# PY32.net
KiCad netlist of a schematic drawn in EasyEDA Pro
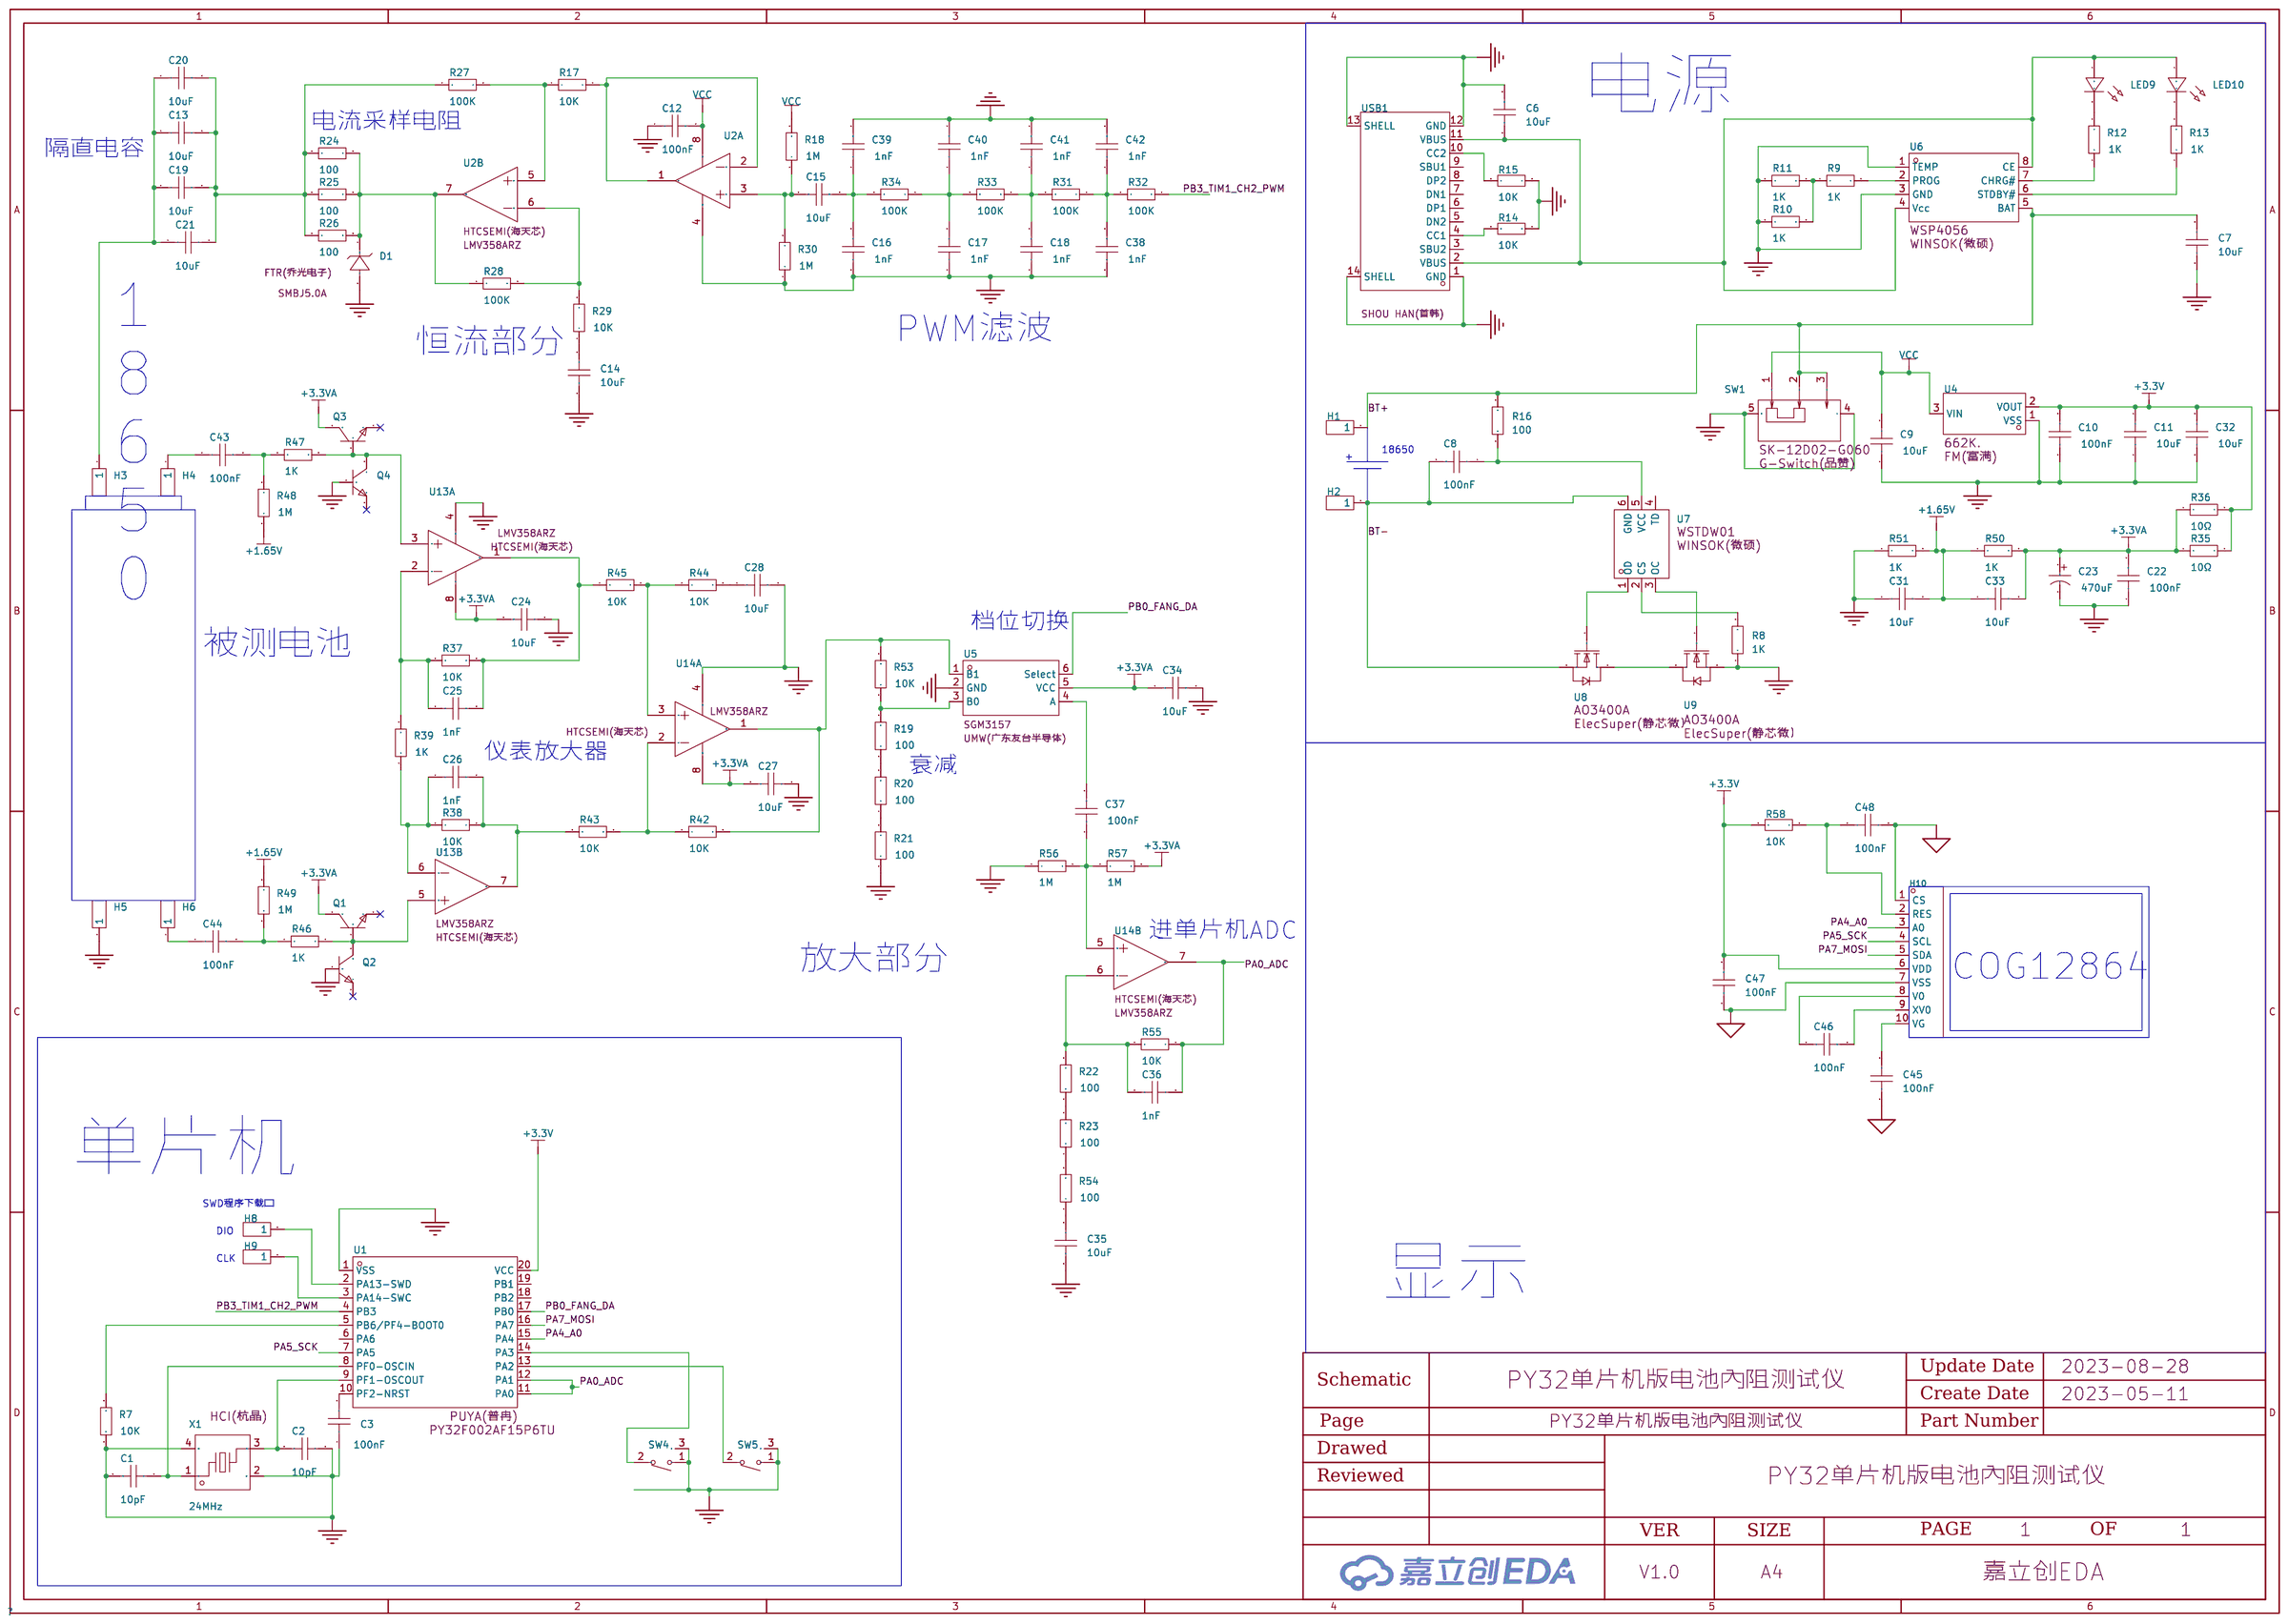
[diagram p0: schematic sheet]

(export (version "E")
  (design (tool "Eeschema 10.0.6"))
  (components
    (comp (ref "C1")
      (value "10pF")
      (footprint "easyedapro:C0603")
      (libsource (lib "easyedapro") (part "CapAcitance"))
    )
    (comp (ref "C2")
      (value "10pF")
      (footprint "easyedapro:C0603")
      (libsource (lib "easyedapro") (part "CapAcitance"))
    )
    (comp (ref "C3")
      (value "100nF")
      (footprint "easyedapro:C0603")
      (libsource (lib "easyedapro") (part "CapAcitance"))
    )
    (comp (ref "C6")
      (value "10uF")
      (footprint "easyedapro:C0603")
      (libsource (lib "easyedapro") (part "CapAcitance"))
    )
    (comp (ref "C7")
      (value "10uF")
      (footprint "easyedapro:C0603")
      (libsource (lib "easyedapro") (part "CapAcitance"))
    )
    (comp (ref "C8")
      (value "100nF")
      (footprint "easyedapro:C0603")
      (libsource (lib "easyedapro") (part "CapAcitance"))
    )
    (comp (ref "C9")
      (value "10uF")
      (footprint "easyedapro:C0603")
      (libsource (lib "easyedapro") (part "CapAcitance"))
    )
    (comp (ref "C10")
      (value "100nF")
      (footprint "easyedapro:C0603")
      (libsource (lib "easyedapro") (part "CapAcitance"))
    )
    (comp (ref "C11")
      (value "10uF")
      (footprint "easyedapro:C0603")
      (libsource (lib "easyedapro") (part "CapAcitance"))
    )
    (comp (ref "C12")
      (value "100nF")
      (footprint "easyedapro:C0603")
      (libsource (lib "easyedapro") (part "CapAcitance"))
    )
    (comp (ref "C13")
      (value "10uF")
      (footprint "easyedapro:C0603")
      (libsource (lib "easyedapro") (part "CapAcitance"))
    )
    (comp (ref "C14")
      (value "10uF")
      (footprint "easyedapro:C0603")
      (libsource (lib "easyedapro") (part "CapAcitance"))
    )
    (comp (ref "C15")
      (value "10uF")
      (footprint "easyedapro:C0603")
      (libsource (lib "easyedapro") (part "CapAcitance"))
    )
    (comp (ref "C16")
      (value "1nF")
      (footprint "easyedapro:C0603")
      (libsource (lib "easyedapro") (part "CapAcitance"))
    )
    (comp (ref "C17")
      (value "1nF")
      (footprint "easyedapro:C0603")
      (libsource (lib "easyedapro") (part "CapAcitance"))
    )
    (comp (ref "C18")
      (value "1nF")
      (footprint "easyedapro:C0603")
      (libsource (lib "easyedapro") (part "CapAcitance"))
    )
    (comp (ref "C19")
      (value "10uF")
      (footprint "easyedapro:C0603")
      (libsource (lib "easyedapro") (part "CapAcitance"))
    )
    (comp (ref "C20")
      (value "10uF")
      (footprint "easyedapro:C0603")
      (libsource (lib "easyedapro") (part "CapAcitance"))
    )
    (comp (ref "C21")
      (value "10uF")
      (footprint "easyedapro:C0603")
      (libsource (lib "easyedapro") (part "CapAcitance"))
    )
    (comp (ref "C22")
      (value "100nF")
      (footprint "easyedapro:C0603")
      (libsource (lib "easyedapro") (part "CapAcitance"))
    )
    (comp (ref "C23")
      (value "470uF")
      (footprint "easyedapro:CAP-TH_BD8.0-P3.50-D0.6-FD")
      (description "容值:470uF;精度:±20%;额定电压:16V;")
      (fields
        (field (name "Manufacturer Part") "KM477M016F12RR0VH2FP0")
        (field (name "Manufacturer") "CX(承兴)")
      )
      (libsource (lib "easyedapro") (part "470uf16v"))
    )
    (comp (ref "C24")
      (value "10uF")
      (footprint "easyedapro:C0603")
      (libsource (lib "easyedapro") (part "CapAcitance"))
    )
    (comp (ref "C25")
      (value "1nF")
      (footprint "easyedapro:C0603")
      (libsource (lib "easyedapro") (part "CapAcitance"))
    )
    (comp (ref "C26")
      (value "1nF")
      (footprint "easyedapro:C0603")
      (libsource (lib "easyedapro") (part "CapAcitance"))
    )
    (comp (ref "C27")
      (value "10uF")
      (footprint "easyedapro:C0603")
      (libsource (lib "easyedapro") (part "CapAcitance"))
    )
    (comp (ref "C28")
      (value "10uF")
      (footprint "easyedapro:C0603")
      (libsource (lib "easyedapro") (part "CapAcitance"))
    )
    (comp (ref "C31")
      (value "10uF")
      (footprint "easyedapro:C0603")
      (libsource (lib "easyedapro") (part "CapAcitance"))
    )
    (comp (ref "C32")
      (value "10uF")
      (footprint "easyedapro:C0603")
      (libsource (lib "easyedapro") (part "CapAcitance"))
    )
    (comp (ref "C33")
      (value "10uF")
      (footprint "easyedapro:C0603")
      (libsource (lib "easyedapro") (part "CapAcitance"))
    )
    (comp (ref "C34")
      (value "10uF")
      (footprint "easyedapro:C0603")
      (libsource (lib "easyedapro") (part "CapAcitance"))
    )
    (comp (ref "C35")
      (value "10uF")
      (footprint "easyedapro:C0603")
      (libsource (lib "easyedapro") (part "CapAcitance"))
    )
    (comp (ref "C36")
      (value "1nF")
      (footprint "easyedapro:C0603")
      (libsource (lib "easyedapro") (part "CapAcitance"))
    )
    (comp (ref "C37")
      (value "100nF")
      (footprint "easyedapro:C0603")
      (libsource (lib "easyedapro") (part "CapAcitance"))
    )
    (comp (ref "C38")
      (value "1nF")
      (footprint "easyedapro:C0603")
      (libsource (lib "easyedapro") (part "CapAcitance"))
    )
    (comp (ref "C39")
      (value "1nF")
      (footprint "easyedapro:C0603")
      (libsource (lib "easyedapro") (part "CapAcitance"))
    )
    (comp (ref "C40")
      (value "1nF")
      (footprint "easyedapro:C0603")
      (libsource (lib "easyedapro") (part "CapAcitance"))
    )
    (comp (ref "C41")
      (value "1nF")
      (footprint "easyedapro:C0603")
      (libsource (lib "easyedapro") (part "CapAcitance"))
    )
    (comp (ref "C42")
      (value "1nF")
      (footprint "easyedapro:C0603")
      (libsource (lib "easyedapro") (part "CapAcitance"))
    )
    (comp (ref "C43")
      (value "100nF")
      (footprint "easyedapro:C1206")
      (description "容值:100nF;精度:±10%;额定电压:450V;材质(温度系数):X7R;")
      (fields (field (name "Manufacturer Part") "FM31X104K451EEG") (field (name "Manufacturer") "PSA(信昌电陶)"))
      (libsource (lib "easyedapro") (part "FM31X104K451EEG"))
    )
    (comp (ref "C44")
      (value "100nF")
      (footprint "easyedapro:C1206")
      (description "容值:100nF;精度:±10%;额定电压:450V;材质(温度系数):X7R;")
      (fields (field (name "Manufacturer Part") "FM31X104K451EEG") (field (name "Manufacturer") "PSA(信昌电陶)"))
      (libsource (lib "easyedapro") (part "FM31X104K451EEG"))
    )
    (comp (ref "C45")
      (value "100nF")
      (footprint "easyedapro:C0603")
      (libsource (lib "easyedapro") (part "CapAcitance"))
    )
    (comp (ref "C46")
      (value "100nF")
      (footprint "easyedapro:C0603")
      (libsource (lib "easyedapro") (part "CapAcitance"))
    )
    (comp (ref "C47")
      (value "100nF")
      (footprint "easyedapro:C0603")
      (libsource (lib "easyedapro") (part "CapAcitance"))
    )
    (comp (ref "C48")
      (value "100nF")
      (footprint "easyedapro:C0603")
      (libsource (lib "easyedapro") (part "CapAcitance"))
    )
    (comp (ref "D1")
      (value "SMBJ5.0A")
      (footprint "easyedapro:SMB_L4.3-W3.6-LS5.3-RD")
      (description "极性:单向;反向截止电压(Vrwm):5V;击穿电压(最小值):6.4V;峰值脉冲电流(Ipp)@10/1000s:65.3A;最大钳位电压:9.2V;")
      (fields (field (name "Manufacturer Part") "SMBJ5.0A") (field (name "Manufacturer") "FTR(乔光电子)"))
      (libsource (lib "easyedapro") (part "SMBJ5.0A_C693503"))
    )
    (comp (ref "H1")
      (value "~")
      (footprint "easyedapro:HDR-TH_1P-V-M_XKB_X4611WV-01I-C28D40")
      (libsource (lib "easyedapro") (part "HDR_1x1"))
    )
    (comp (ref "H2")
      (value "~")
      (footprint "easyedapro:HDR-TH_1P-V-M_XKB_X4611WV-01I-C28D40")
      (libsource (lib "easyedapro") (part "HDR_1x1"))
    )
    (comp (ref "H3")
      (value "~")
      (footprint "easyedapro:HDR-TH_1P-V-M_XKB_X4611WV-01I-C28D40")
      (libsource (lib "easyedapro") (part "HDR_1x1"))
    )
    (comp (ref "H4")
      (value "~")
      (footprint "easyedapro:HDR-TH_1P-V-M_XKB_X4611WV-01I-C28D40")
      (libsource (lib "easyedapro") (part "HDR_1x1"))
    )
    (comp (ref "H5")
      (value "~")
      (footprint "easyedapro:HDR-TH_1P-V-M_XKB_X4611WV-01I-C28D40")
      (libsource (lib "easyedapro") (part "HDR_1x1"))
    )
    (comp (ref "H6")
      (value "~")
      (footprint "easyedapro:HDR-TH_1P-V-M_XKB_X4611WV-01I-C28D40")
      (libsource (lib "easyedapro") (part "HDR_1x1"))
    )
    (comp (ref "H8")
      (value "~")
      (footprint "easyedapro:HDR-TH_1P-V-M_XKB_X4611WV-01I-C28D40")
      (libsource (lib "easyedapro") (part "HDR_1x1"))
    )
    (comp (ref "H9")
      (value "~")
      (footprint "easyedapro:HDR-TH_1P-V-M_XKB_X4611WV-01I-C28D40")
      (libsource (lib "easyedapro") (part "HDR_1x1"))
    )
    (comp (ref "H10")
      (value "~")
      (footprint "easyedapro:HDR-TH_10P-P2.54-V-M-1")
      (fields (field (name "Manufacturer Part") "2.54-1*10P针") (field (name "Manufacturer") "BOOMELE(博穆精密)"))
      (libsource (lib "easyedapro") (part "Header-Male-2.54_1x10"))
    )
    (comp (ref "LED9")
      (value "~")
      (footprint "easyedapro:LED_TH-3mm")
      (libsource (lib "easyedapro") (part "LED_TH-R"))
    )
    (comp (ref "LED10")
      (value "~")
      (footprint "easyedapro:LED_TH-3mm")
      (libsource (lib "easyedapro") (part "LED_TH-R"))
    )
    (comp (ref "Q1")
      (value "SS8050")
      (footprint "easyedapro:SOT-23-3_L2.9-W1.3-P1.90-LS2.4-BR")
      (fields (field (name "Manufacturer") "ElecSuper(静芯微）"))
      (libsource (lib "easyedapro") (part "SS8050_C5249676"))
    )
    (comp (ref "Q2")
      (value "SS8050")
      (footprint "easyedapro:SOT-23-3_L2.9-W1.3-P1.90-LS2.4-BR")
      (fields (field (name "Manufacturer") "ElecSuper(静芯微）"))
      (libsource (lib "easyedapro") (part "SS8050_C5249676"))
    )
    (comp (ref "Q3")
      (value "SS8050")
      (footprint "easyedapro:SOT-23-3_L2.9-W1.3-P1.90-LS2.4-BR")
      (fields (field (name "Manufacturer") "ElecSuper(静芯微）"))
      (libsource (lib "easyedapro") (part "SS8050_C5249676"))
    )
    (comp (ref "Q4")
      (value "SS8050")
      (footprint "easyedapro:SOT-23-3_L2.9-W1.3-P1.90-LS2.4-BR")
      (fields (field (name "Manufacturer") "ElecSuper(静芯微）"))
      (libsource (lib "easyedapro") (part "SS8050_C5249676"))
    )
    (comp (ref "R7") (value "10K") (footprint "easyedapro:R0603") (libsource (lib "easyedapro") (part "电阻")))
    (comp (ref "R8") (value "1K") (footprint "easyedapro:R0603") (libsource (lib "easyedapro") (part "电阻")))
    (comp (ref "R9") (value "1K") (footprint "easyedapro:R0603") (libsource (lib "easyedapro") (part "电阻")))
    (comp (ref "R10") (value "1K") (footprint "easyedapro:R0603") (libsource (lib "easyedapro") (part "电阻")))
    (comp (ref "R11") (value "1K") (footprint "easyedapro:R0603") (libsource (lib "easyedapro") (part "电阻")))
    (comp (ref "R12") (value "1K") (footprint "easyedapro:R0603") (libsource (lib "easyedapro") (part "电阻")))
    (comp (ref "R13") (value "1K") (footprint "easyedapro:R0603") (libsource (lib "easyedapro") (part "电阻")))
    (comp (ref "R14") (value "10K") (footprint "easyedapro:R0603") (libsource (lib "easyedapro") (part "电阻")))
    (comp (ref "R15") (value "10K") (footprint "easyedapro:R0603") (libsource (lib "easyedapro") (part "电阻")))
    (comp (ref "R16") (value "100") (footprint "easyedapro:R0603") (libsource (lib "easyedapro") (part "电阻")))
    (comp (ref "R17") (value "10K") (footprint "easyedapro:R0603") (libsource (lib "easyedapro") (part "电阻")))
    (comp (ref "R18") (value "1M") (footprint "easyedapro:R0603") (libsource (lib "easyedapro") (part "电阻")))
    (comp (ref "R19") (value "100") (footprint "easyedapro:R0603") (libsource (lib "easyedapro") (part "电阻")))
    (comp (ref "R20") (value "100") (footprint "easyedapro:R0603") (libsource (lib "easyedapro") (part "电阻")))
    (comp (ref "R21") (value "100") (footprint "easyedapro:R0603") (libsource (lib "easyedapro") (part "电阻")))
    (comp (ref "R22") (value "100") (footprint "easyedapro:R0603") (libsource (lib "easyedapro") (part "电阻")))
    (comp (ref "R23") (value "100") (footprint "easyedapro:R0603") (libsource (lib "easyedapro") (part "电阻")))
    (comp (ref "R24") (value "100") (footprint "easyedapro:R0603") (libsource (lib "easyedapro") (part "电阻")))
    (comp (ref "R25") (value "100") (footprint "easyedapro:R0603") (libsource (lib "easyedapro") (part "电阻")))
    (comp (ref "R26") (value "100") (footprint "easyedapro:R0603") (libsource (lib "easyedapro") (part "电阻")))
    (comp (ref "R27")
      (value "100K")
      (footprint "easyedapro:R0603")
      (libsource (lib "easyedapro") (part "电阻"))
    )
    (comp (ref "R28")
      (value "100K")
      (footprint "easyedapro:R0603")
      (libsource (lib "easyedapro") (part "电阻"))
    )
    (comp (ref "R29") (value "10K") (footprint "easyedapro:R0603") (libsource (lib "easyedapro") (part "电阻")))
    (comp (ref "R30") (value "1M") (footprint "easyedapro:R0603") (libsource (lib "easyedapro") (part "电阻")))
    (comp (ref "R31")
      (value "100K")
      (footprint "easyedapro:R0603")
      (libsource (lib "easyedapro") (part "电阻"))
    )
    (comp (ref "R32")
      (value "100K")
      (footprint "easyedapro:R0603")
      (libsource (lib "easyedapro") (part "电阻"))
    )
    (comp (ref "R33")
      (value "100K")
      (footprint "easyedapro:R0603")
      (libsource (lib "easyedapro") (part "电阻"))
    )
    (comp (ref "R34")
      (value "100K")
      (footprint "easyedapro:R0603")
      (libsource (lib "easyedapro") (part "电阻"))
    )
    (comp (ref "R35") (value "10Ω") (footprint "easyedapro:R0603") (libsource (lib "easyedapro") (part "电阻")))
    (comp (ref "R36") (value "10Ω") (footprint "easyedapro:R0603") (libsource (lib "easyedapro") (part "电阻")))
    (comp (ref "R37") (value "10K") (footprint "easyedapro:R0603") (libsource (lib "easyedapro") (part "电阻")))
    (comp (ref "R38") (value "10K") (footprint "easyedapro:R0603") (libsource (lib "easyedapro") (part "电阻")))
    (comp (ref "R39") (value "1K") (footprint "easyedapro:R0603") (libsource (lib "easyedapro") (part "电阻")))
    (comp (ref "R42") (value "10K") (footprint "easyedapro:R0603") (libsource (lib "easyedapro") (part "电阻")))
    (comp (ref "R43") (value "10K") (footprint "easyedapro:R0603") (libsource (lib "easyedapro") (part "电阻")))
    (comp (ref "R44") (value "10K") (footprint "easyedapro:R0603") (libsource (lib "easyedapro") (part "电阻")))
    (comp (ref "R45") (value "10K") (footprint "easyedapro:R0603") (libsource (lib "easyedapro") (part "电阻")))
    (comp (ref "R46") (value "1K") (footprint "easyedapro:R0603") (libsource (lib "easyedapro") (part "电阻")))
    (comp (ref "R47") (value "1K") (footprint "easyedapro:R0603") (libsource (lib "easyedapro") (part "电阻")))
    (comp (ref "R48") (value "1M") (footprint "easyedapro:R0603") (libsource (lib "easyedapro") (part "电阻")))
    (comp (ref "R49") (value "1M") (footprint "easyedapro:R0603") (libsource (lib "easyedapro") (part "电阻")))
    (comp (ref "R50") (value "1K") (footprint "easyedapro:R0603") (libsource (lib "easyedapro") (part "电阻")))
    (comp (ref "R51") (value "1K") (footprint "easyedapro:R0603") (libsource (lib "easyedapro") (part "电阻")))
    (comp (ref "R53") (value "10K") (footprint "easyedapro:R0603") (libsource (lib "easyedapro") (part "电阻")))
    (comp (ref "R54") (value "100") (footprint "easyedapro:R0603") (libsource (lib "easyedapro") (part "电阻")))
    (comp (ref "R55") (value "10K") (footprint "easyedapro:R0603") (libsource (lib "easyedapro") (part "电阻")))
    (comp (ref "R56") (value "1M") (footprint "easyedapro:R0603") (libsource (lib "easyedapro") (part "电阻")))
    (comp (ref "R57") (value "1M") (footprint "easyedapro:R0603") (libsource (lib "easyedapro") (part "电阻")))
    (comp (ref "R58") (value "10K") (footprint "easyedapro:R0603") (libsource (lib "easyedapro") (part "电阻")))
    (comp (ref "SW1")
      (value "SK-12D02-G060")
      (footprint "easyedapro:SW-TH_SK-12D02-G060")
      (description "额定电流(DC):1A;额定电压(DC):24V;电路结构:单刀双掷;安装方式:卧插;机械寿命:1万次;开关颜色:黑色;")
      (fields (field (name "Manufacturer Part") "SK-12D02-G060") (field (name "Manufacturer") "G-Switch(品赞)"))
      (libsource (lib "easyedapro") (part "SK-12D02-G060"))
    )
    (comp (ref "SW4")
      (value "HX TS4538B3J 250gf")
      (footprint "easyedapro:SW-TH_TS4538B3J")
      (description "机械寿命:-;")
      (fields (field (name "Manufacturer") "hanxia(韩下)"))
      (libsource (lib "easyedapro") (part "HX TS4538B3J 250GF"))
    )
    (comp (ref "SW5")
      (value "HX TS4538B3J 250gf")
      (footprint "easyedapro:SW-TH_TS4538B3J")
      (description "机械寿命:-;")
      (fields (field (name "Manufacturer") "hanxia(韩下)"))
      (libsource (lib "easyedapro") (part "HX TS4538B3J 250GF"))
    )
    (comp (ref "U1")
      (value "PY32F002AF15P6TU")
      (footprint "easyedapro:TSSOP-20_L6.5-W4.4-P0.65-LS6.4-BL")
      (fields (field (name "Manufacturer Part") "PY32F002AF15P6TU") (field (name "Manufacturer") "PUYA(普冉)"))
      (libsource (lib "easyedapro") (part "PY32F002AF15P6TU"))
    )
    (comp (ref "U2")
      (value "LMV358ARZ")
      (footprint "easyedapro:SOP-8_L4.9-W3.9-P1.27-LS6.0-BL")
      (description "CMOS低功耗双路运算放大器")
      (fields (field (name "Manufacturer Part") "LMV358ARZ") (field (name "Manufacturer") "HTCSEMI(海天芯)"))
      (libsource (lib "easyedapro") (part "LMV358ARZ"))
    )
    (comp (ref "U4")
      (value "662K.")
      (footprint "easyedapro:SOT-23-3_L2.9-W1.3-P1.90-LS2.4-BR")
      (description "输出类型:-;")
      (fields (field (name "Manufacturer Part") "662K.") (field (name "Manufacturer") "FM(富满)"))
      (libsource (lib "easyedapro") (part "662K."))
    )
    (comp (ref "U5")
      (value "SGM3157")
      (footprint "easyedapro:SC-70-6_L2.2-W1.3-P0.65-LS2.1-BL")
      (description "开关电路:-;")
      (fields (field (name "Manufacturer Part") "SGM3157") (field (name "Manufacturer") "UMW(广东友台半导体)"))
      (libsource (lib "easyedapro") (part "SGM3157"))
    )
    (comp (ref "U6")
      (value "WSP4056")
      (footprint "easyedapro:SOP-8_L5.1-W3.9-P1.27-LS6.0-BL")
      (fields (field (name "Manufacturer Part") "WSP4056") (field (name "Manufacturer") "WINSOK(微硕)"))
      (libsource (lib "easyedapro") (part "WSP4056"))
    )
    (comp (ref "U7")
      (value "WSTDW01")
      (footprint "easyedapro:SOT-23-6_L2.9-W1.6-P0.95-LS2.8-BR")
      (description "充电电池的类型:-;电池单元组数:-;最大充电电流:-;充满的电池组电压:-;最大供应电压:-;")
      (fields (field (name "Manufacturer Part") "WSTDW01") (field (name "Manufacturer") "WINSOK(微硕)"))
      (libsource (lib "easyedapro") (part "WSTDW01"))
    )
    (comp (ref "U8")
      (value "AO3400A")
      (footprint "easyedapro:SOT-23-3_L3.0-W1.6-P1.90-LS2.8-BR")
      (description "类型:N沟道;漏源电压(Vdss):30V;连续漏极电流(Id):6A;功率(Pd):1.4W;导通电阻(RDS(on)@Vgs,Id):19mΩ@10V,6.0A;")
      (fields (field (name "Manufacturer Part") "AO3400A") (field (name "Manufacturer") "ElecSuper(静芯微）"))
      (libsource (lib "easyedapro") (part "AO3400A_C5224194"))
    )
    (comp (ref "U9")
      (value "AO3400A")
      (footprint "easyedapro:SOT-23-3_L3.0-W1.6-P1.90-LS2.8-BR")
      (description "类型:N沟道;漏源电压(Vdss):30V;连续漏极电流(Id):6A;功率(Pd):1.4W;导通电阻(RDS(on)@Vgs,Id):19mΩ@10V,6.0A;")
      (fields (field (name "Manufacturer Part") "AO3400A") (field (name "Manufacturer") "ElecSuper(静芯微）"))
      (libsource (lib "easyedapro") (part "AO3400A_C5224194"))
    )
    (comp (ref "U13")
      (value "LMV358ARZ")
      (footprint "easyedapro:SOP-8_L4.9-W3.9-P1.27-LS6.0-BL")
      (description "CMOS低功耗双路运算放大器")
      (fields (field (name "Manufacturer Part") "LMV358ARZ") (field (name "Manufacturer") "HTCSEMI(海天芯)"))
      (libsource (lib "easyedapro") (part "LMV358ARZ"))
    )
    (comp (ref "U14")
      (value "LMV358ARZ")
      (footprint "easyedapro:SOP-8_L4.9-W3.9-P1.27-LS6.0-BL")
      (description "CMOS低功耗双路运算放大器")
      (fields (field (name "Manufacturer Part") "LMV358ARZ") (field (name "Manufacturer") "HTCSEMI(海天芯)"))
      (libsource (lib "easyedapro") (part "LMV358ARZ"))
    )
    (comp (ref "USB1")
      (value "TYPE-C 16PIN 2MD(073)")
      (footprint "easyedapro:USB-C-SMD_TYPE-C-6PIN-2MD-073")
      (description "连接器类型:Type-C;标准:-;公母:母座;触点数量:16;端口数量:1;安装方式:卧贴;额定电流 - 电源:5A;工作温度范围:-25°C~+85°C;")
      (fields (field (name "Manufacturer") "SHOU HAN(首韩)"))
      (libsource (lib "easyedapro") (part "TYPE-C 16PIN 2MD(073)"))
    )
    (comp (ref "X1")
      (value "24MHz")
      (footprint "easyedapro:CRYSTAL-SMD_4P-L3.2-W2.5-BL")
      (description "频率:24MHz;频率公差:±10ppm;频率稳定度:±30ppm;负载电容:12pF;")
      (fields
        (field (name "Manufacturer Part") "XC32M4-24.000-F12NJDTL")
        (field (name "Manufacturer") "HCI(杭晶)")
      )
      (libsource (lib "easyedapro") (part "XC32M4-24.000-F12NJDTL"))
    )
  )
  (nets
    (net (code "1") (name "+1.65V") (class "Default")
      (node (ref "C31") (pin "2") (pinfunction "2_2") (pintype "input"))
      (node (ref "C33") (pin "1") (pinfunction "1_1") (pintype "input"))
      (node (ref "R48") (pin "1") (pinfunction "1_1") (pintype "input"))
      (node (ref "R49") (pin "2") (pinfunction "2_2") (pintype "input"))
      (node (ref "R50") (pin "1") (pinfunction "1_1") (pintype "input"))
      (node (ref "R51") (pin "2") (pinfunction "2_2") (pintype "input"))
    )
    (net (code "2") (name "+3.3V") (class "Default")
      (node (ref "C10") (pin "2") (pinfunction "2_2") (pintype "input"))
      (node (ref "C11") (pin "2") (pinfunction "2_2") (pintype "input"))
      (node (ref "C32") (pin "2") (pinfunction "2_2") (pintype "input"))
      (node (ref "C47") (pin "2") (pinfunction "2_2") (pintype "input"))
      (node (ref "H10") (pin "6") (pinfunction "VDD_6") (pintype "input"))
      (node (ref "R35") (pin "2") (pinfunction "2_2") (pintype "input"))
      (node (ref "R36") (pin "2") (pinfunction "2_2") (pintype "input"))
      (node (ref "R58") (pin "1") (pinfunction "1_1") (pintype "input"))
      (node (ref "U1") (pin "20") (pinfunction "VCC_20") (pintype "input"))
      (node (ref "U4") (pin "2") (pinfunction "VOUT_2") (pintype "input"))
    )
    (net (code "3") (name "+3.3VA") (class "Default")
      (node (ref "C22") (pin "2") (pinfunction "2_2") (pintype "input"))
      (node (ref "C23") (pin "1") (pinfunction "1_1") (pintype "input"))
      (node (ref "C24") (pin "2") (pinfunction "2_2") (pintype "input"))
      (node (ref "C27") (pin "1") (pinfunction "1_1") (pintype "input"))
      (node (ref "C33") (pin "2") (pinfunction "2_2") (pintype "input"))
      (node (ref "C34") (pin "1") (pinfunction "1_1") (pintype "input"))
      (node (ref "Q1") (pin "3") (pinfunction "C_3") (pintype "input"))
      (node (ref "Q3") (pin "3") (pinfunction "C_3") (pintype "input"))
      (node (ref "R35") (pin "1") (pinfunction "1_1") (pintype "input"))
      (node (ref "R36") (pin "1") (pinfunction "1_1") (pintype "input"))
      (node (ref "R50") (pin "2") (pinfunction "2_2") (pintype "input"))
      (node (ref "R57") (pin "2") (pinfunction "2_2") (pintype "input"))
      (node (ref "U13") (pin "8") (pinfunction "VCC_8") (pintype "input"))
      (node (ref "U14") (pin "8") (pinfunction "VCC_8") (pintype "input"))
      (node (ref "U5") (pin "5") (pinfunction "VCC_5") (pintype "input"))
    )
    (net (code "4") (name "/BT+") (class "Default")
      (node (ref "C7") (pin "2") (pinfunction "2_2") (pintype "input"))
      (node (ref "H1") (pin "1") (pinfunction "1_1") (pintype "unspecified"))
      (node (ref "R16") (pin "2") (pinfunction "2_2") (pintype "input"))
      (node (ref "SW1") (pin "2") (pinfunction "2_2") (pintype "input"))
      (node (ref "SW1") (pin "3") (pinfunction "3_3") (pintype "input"))
      (node (ref "U6") (pin "5") (pinfunction "BAT_5") (pintype "input"))
    )
    (net (code "5") (name "/BT-") (class "Default")
      (node (ref "C8") (pin "2") (pinfunction "2_2") (pintype "input"))
      (node (ref "H2") (pin "1") (pinfunction "1_1") (pintype "unspecified"))
      (node (ref "U7") (pin "6") (pinfunction "GND_6") (pintype "input"))
      (node (ref "U8") (pin "2") (pinfunction "S_2") (pintype "input"))
    )
    (net (code "6") (name "/PA0_ADC") (class "Default")
      (node (ref "C36") (pin "2") (pinfunction "2_2") (pintype "input"))
      (node (ref "R55") (pin "2") (pinfunction "2_2") (pintype "input"))
      (node (ref "U1") (pin "11") (pinfunction "PA0_11") (pintype "input"))
      (node (ref "U1") (pin "12") (pinfunction "PA1_12") (pintype "input"))
      (node (ref "U14") (pin "7") (pinfunction "OUT2_7") (pintype "output"))
    )
    (net (code "7") (name "/PA4_A0") (class "Default")
      (node (ref "H10") (pin "3") (pinfunction "A0_3") (pintype "input"))
      (node (ref "U1") (pin "15") (pinfunction "PA4_15") (pintype "input"))
    )
    (net (code "8") (name "/PA5_SCK") (class "Default")
      (node (ref "H10") (pin "4") (pinfunction "SCL_4") (pintype "input"))
      (node (ref "U1") (pin "7") (pinfunction "PA5_7") (pintype "input"))
    )
    (net (code "9") (name "/PA7_MOSI") (class "Default")
      (node (ref "H10") (pin "5") (pinfunction "SDA_5") (pintype "input"))
      (node (ref "U1") (pin "16") (pinfunction "PA7_16") (pintype "input"))
    )
    (net (code "10") (name "/PB0_FANG_DA") (class "Default")
      (node (ref "U1") (pin "17") (pinfunction "PB0_17") (pintype "input"))
      (node (ref "U5") (pin "6") (pinfunction "Select_6") (pintype "input"))
    )
    (net (code "11") (name "/PB3_TIM1_CH2_PWM") (class "Default")
      (node (ref "R32") (pin "1") (pinfunction "1_1") (pintype "input"))
      (node (ref "U1") (pin "4") (pinfunction "PB3_4") (pintype "input"))
    )
    (net (code "12") (name "AGND") (class "Default")
      (node (ref "C45") (pin "1") (pinfunction "1_1") (pintype "input"))
      (node (ref "C47") (pin "1") (pinfunction "1_1") (pintype "input"))
      (node (ref "C48") (pin "2") (pinfunction "2_2") (pintype "input"))
      (node (ref "H10") (pin "1") (pinfunction "CS_1") (pintype "input"))
      (node (ref "H10") (pin "7") (pinfunction "VSS_7") (pintype "input"))
    )
    (net (code "13") (name "GND") (class "Default")
      (node (ref "C1") (pin "2") (pinfunction "2_2") (pintype "input"))
      (node (ref "C10") (pin "1") (pinfunction "1_1") (pintype "input"))
      (node (ref "C11") (pin "1") (pinfunction "1_1") (pintype "input"))
      (node (ref "C12") (pin "1") (pinfunction "1_1") (pintype "input"))
      (node (ref "C14") (pin "1") (pinfunction "1_1") (pintype "input"))
      (node (ref "C16") (pin "1") (pinfunction "1_1") (pintype "input"))
      (node (ref "C17") (pin "1") (pinfunction "1_1") (pintype "input"))
      (node (ref "C18") (pin "1") (pinfunction "1_1") (pintype "input"))
      (node (ref "C2") (pin "1") (pinfunction "1_1") (pintype "input"))
      (node (ref "C22") (pin "1") (pinfunction "1_1") (pintype "input"))
      (node (ref "C23") (pin "2") (pinfunction "2_2") (pintype "input"))
      (node (ref "C24") (pin "1") (pinfunction "1_1") (pintype "input"))
      (node (ref "C27") (pin "2") (pinfunction "2_2") (pintype "input"))
      (node (ref "C28") (pin "2") (pinfunction "2_2") (pintype "input"))
      (node (ref "C3") (pin "1") (pinfunction "1_1") (pintype "input"))
      (node (ref "C31") (pin "1") (pinfunction "1_1") (pintype "input"))
      (node (ref "C32") (pin "1") (pinfunction "1_1") (pintype "input"))
      (node (ref "C34") (pin "2") (pinfunction "2_2") (pintype "input"))
      (node (ref "C35") (pin "1") (pinfunction "1_1") (pintype "input"))
      (node (ref "C38") (pin "1") (pinfunction "1_1") (pintype "input"))
      (node (ref "C39") (pin "2") (pinfunction "2_2") (pintype "input"))
      (node (ref "C40") (pin "2") (pinfunction "2_2") (pintype "input"))
      (node (ref "C41") (pin "2") (pinfunction "2_2") (pintype "input"))
      (node (ref "C42") (pin "2") (pinfunction "2_2") (pintype "input"))
      (node (ref "C6") (pin "2") (pinfunction "2_2") (pintype "input"))
      (node (ref "C7") (pin "1") (pinfunction "1_1") (pintype "input"))
      (node (ref "C9") (pin "1") (pinfunction "1_1") (pintype "input"))
      (node (ref "D1") (pin "2") (pinfunction "A_2") (pintype "input"))
      (node (ref "H5") (pin "1") (pinfunction "1_1") (pintype "unspecified"))
      (node (ref "Q2") (pin "1") (pinfunction "B_1") (pintype "input"))
      (node (ref "Q4") (pin "1") (pinfunction "B_1") (pintype "input"))
      (node (ref "R10") (pin "1") (pinfunction "1_1") (pintype "input"))
      (node (ref "R11") (pin "1") (pinfunction "1_1") (pintype "input"))
      (node (ref "R14") (pin "1") (pinfunction "1_1") (pintype "input"))
      (node (ref "R15") (pin "1") (pinfunction "1_1") (pintype "input"))
      (node (ref "R21") (pin "1") (pinfunction "1_1") (pintype "input"))
      (node (ref "R30") (pin "1") (pinfunction "1_1") (pintype "input"))
      (node (ref "R51") (pin "1") (pinfunction "1_1") (pintype "input"))
      (node (ref "R56") (pin "1") (pinfunction "1_1") (pintype "input"))
      (node (ref "R7") (pin "1") (pinfunction "1_1") (pintype "input"))
      (node (ref "R8") (pin "1") (pinfunction "1_1") (pintype "input"))
      (node (ref "SW1") (pin "4") (pinfunction "4_4") (pintype "input"))
      (node (ref "SW1") (pin "5") (pinfunction "5_5") (pintype "input"))
      (node (ref "SW4") (pin "1") (pinfunction "1_1") (pintype "input"))
      (node (ref "SW4") (pin "3") (pinfunction "3_3") (pintype "input"))
      (node (ref "SW5") (pin "1") (pinfunction "1_1") (pintype "input"))
      (node (ref "SW5") (pin "3") (pinfunction "3_3") (pintype "input"))
      (node (ref "U1") (pin "1") (pinfunction "VSS_1") (pintype "input"))
      (node (ref "U13") (pin "4") (pinfunction "GND_4") (pintype "input"))
      (node (ref "U14") (pin "4") (pinfunction "GND_4") (pintype "input"))
      (node (ref "U2") (pin "4") (pinfunction "GND_4") (pintype "input"))
      (node (ref "U4") (pin "1") (pinfunction "VSS_1") (pintype "input"))
      (node (ref "U5") (pin "2") (pinfunction "GND_2") (pintype "input"))
      (node (ref "U6") (pin "1") (pinfunction "TEMP_1") (pintype "input"))
      (node (ref "U6") (pin "3") (pinfunction "GND_3") (pintype "input"))
      (node (ref "U9") (pin "2") (pinfunction "S_2") (pintype "input"))
      (node (ref "USB1") (pin "1") (pinfunction "GND_1") (pintype "input"))
      (node (ref "USB1") (pin "12") (pinfunction "GND_12") (pintype "input"))
      (node (ref "USB1") (pin "13") (pinfunction "SHELL_13") (pintype "input"))
      (node (ref "USB1") (pin "14") (pinfunction "SHELL_14") (pintype "input"))
      (node (ref "X1") (pin "2") (pinfunction "GND_2") (pintype "input"))
      (node (ref "X1") (pin "4") (pinfunction "GND_4") (pintype "input"))
    )
    (net (code "14") (name "Net-(C13-Pad1)") (class "Default")
      (node (ref "C13") (pin "1") (pinfunction "1_1") (pintype "input"))
      (node (ref "C19") (pin "1") (pinfunction "1_1") (pintype "input"))
      (node (ref "C20") (pin "1") (pinfunction "1_1") (pintype "input"))
      (node (ref "C21") (pin "1") (pinfunction "1_1") (pintype "input"))
      (node (ref "H3") (pin "1") (pinfunction "1_1") (pintype "unspecified"))
    )
    (net (code "15") (name "Net-(C13-Pad2)") (class "Default")
      (node (ref "C13") (pin "2") (pinfunction "2_2") (pintype "input"))
      (node (ref "C19") (pin "2") (pinfunction "2_2") (pintype "input"))
      (node (ref "C20") (pin "2") (pinfunction "2_2") (pintype "input"))
      (node (ref "C21") (pin "2") (pinfunction "2_2") (pintype "input"))
      (node (ref "R24") (pin "1") (pinfunction "1_1") (pintype "input"))
      (node (ref "R25") (pin "1") (pinfunction "1_1") (pintype "input"))
      (node (ref "R26") (pin "1") (pinfunction "1_1") (pintype "input"))
      (node (ref "R27") (pin "1") (pinfunction "1_1") (pintype "input"))
    )
    (net (code "16") (name "Net-(C14-Pad2)") (class "Default")
      (node (ref "C14") (pin "2") (pinfunction "2_2") (pintype "input"))
      (node (ref "R29") (pin "1") (pinfunction "1_1") (pintype "input"))
    )
    (net (code "17") (name "Net-(C15-Pad2)") (class "Default")
      (node (ref "C15") (pin "2") (pinfunction "2_2") (pintype "input"))
      (node (ref "C16") (pin "2") (pinfunction "2_2") (pintype "input"))
      (node (ref "C39") (pin "1") (pinfunction "1_1") (pintype "input"))
      (node (ref "R34") (pin "2") (pinfunction "2_2") (pintype "input"))
    )
    (net (code "18") (name "Net-(C17-Pad2)") (class "Default")
      (node (ref "C17") (pin "2") (pinfunction "2_2") (pintype "input"))
      (node (ref "C40") (pin "1") (pinfunction "1_1") (pintype "input"))
      (node (ref "R33") (pin "2") (pinfunction "2_2") (pintype "input"))
      (node (ref "R34") (pin "1") (pinfunction "1_1") (pintype "input"))
    )
    (net (code "19") (name "Net-(C18-Pad2)") (class "Default")
      (node (ref "C18") (pin "2") (pinfunction "2_2") (pintype "input"))
      (node (ref "C41") (pin "1") (pinfunction "1_1") (pintype "input"))
      (node (ref "R31") (pin "2") (pinfunction "2_2") (pintype "input"))
      (node (ref "R33") (pin "1") (pinfunction "1_1") (pintype "input"))
    )
    (net (code "20") (name "Net-(C28-Pad1)") (class "Default")
      (node (ref "C28") (pin "1") (pinfunction "1_1") (pintype "input"))
      (node (ref "R44") (pin "2") (pinfunction "2_2") (pintype "input"))
    )
    (net (code "21") (name "Net-(C35-Pad2)") (class "Default")
      (node (ref "C35") (pin "2") (pinfunction "2_2") (pintype "input"))
      (node (ref "R54") (pin "1") (pinfunction "1_1") (pintype "input"))
    )
    (net (code "22") (name "Net-(C38-Pad2)") (class "Default")
      (node (ref "C38") (pin "2") (pinfunction "2_2") (pintype "input"))
      (node (ref "C42") (pin "1") (pinfunction "1_1") (pintype "input"))
      (node (ref "R31") (pin "1") (pinfunction "1_1") (pintype "input"))
      (node (ref "R32") (pin "2") (pinfunction "2_2") (pintype "input"))
    )
    (net (code "23") (name "Net-(C43-Pad1)") (class "Default")
      (node (ref "C43") (pin "1") (pinfunction "1_1") (pintype "input"))
      (node (ref "H4") (pin "1") (pinfunction "1_1") (pintype "unspecified"))
    )
    (net (code "24") (name "Net-(C43-Pad2)") (class "Default")
      (node (ref "C43") (pin "2") (pinfunction "2_2") (pintype "input"))
      (node (ref "R47") (pin "1") (pinfunction "1_1") (pintype "input"))
      (node (ref "R48") (pin "2") (pinfunction "2_2") (pintype "input"))
    )
    (net (code "25") (name "Net-(C44-Pad1)") (class "Default")
      (node (ref "C44") (pin "1") (pinfunction "1_1") (pintype "input"))
      (node (ref "H6") (pin "1") (pinfunction "1_1") (pintype "unspecified"))
    )
    (net (code "26") (name "Net-(C44-Pad2)") (class "Default")
      (node (ref "C44") (pin "2") (pinfunction "2_2") (pintype "input"))
      (node (ref "R46") (pin "1") (pinfunction "1_1") (pintype "input"))
      (node (ref "R49") (pin "1") (pinfunction "1_1") (pintype "input"))
    )
    (net (code "27") (name "Net-(D1-C)") (class "Default")
      (node (ref "D1") (pin "1") (pinfunction "C_1") (pintype "input"))
      (node (ref "R24") (pin "2") (pinfunction "2_2") (pintype "input"))
      (node (ref "R25") (pin "2") (pinfunction "2_2") (pintype "input"))
      (node (ref "R26") (pin "2") (pinfunction "2_2") (pintype "input"))
      (node (ref "R28") (pin "1") (pinfunction "1_1") (pintype "input"))
      (node (ref "U2") (pin "7") (pinfunction "OUT2_7") (pintype "output"))
    )
    (net (code "28") (name "Net-(H10-RES)") (class "Default")
      (node (ref "C48") (pin "1") (pinfunction "1_1") (pintype "input"))
      (node (ref "H10") (pin "2") (pinfunction "RES_2") (pintype "input"))
      (node (ref "R58") (pin "2") (pinfunction "2_2") (pintype "input"))
    )
    (net (code "29") (name "Net-(H10-V0)") (class "Default")
      (node (ref "C46") (pin "1") (pinfunction "1_1") (pintype "input"))
      (node (ref "H10") (pin "8") (pinfunction "V0_8") (pintype "input"))
    )
    (net (code "30") (name "Net-(H10-VG)") (class "Default")
      (node (ref "C45") (pin "2") (pinfunction "2_2") (pintype "input"))
      (node (ref "H10") (pin "10") (pinfunction "VG_10") (pintype "input"))
    )
    (net (code "31") (name "Net-(H10-XV0)") (class "Default")
      (node (ref "C46") (pin "2") (pinfunction "2_2") (pintype "input"))
      (node (ref "H10") (pin "9") (pinfunction "XV0_9") (pintype "input"))
    )
    (net (code "32") (name "Net-(LED9-A)") (class "Default")
      (node (ref "LED9") (pin "2") (pinfunction "A_2") (pintype "input"))
      (node (ref "R12") (pin "2") (pinfunction "2_2") (pintype "input"))
    )
    (net (code "33") (name "Net-(LED10-A)") (class "Default")
      (node (ref "LED10") (pin "2") (pinfunction "A_2") (pintype "input"))
      (node (ref "R13") (pin "2") (pinfunction "2_2") (pintype "input"))
    )
    (net (code "34") (name "Net-(LED10-C)") (class "Default")
      (node (ref "C6") (pin "1") (pinfunction "1_1") (pintype "input"))
      (node (ref "LED10") (pin "1") (pinfunction "C_1") (pintype "input"))
      (node (ref "LED9") (pin "1") (pinfunction "C_1") (pintype "input"))
      (node (ref "U6") (pin "4") (pinfunction "Vcc_4") (pintype "input"))
      (node (ref "U6") (pin "8") (pinfunction "CE_8") (pintype "input"))
      (node (ref "USB1") (pin "11") (pinfunction "VBUS_11") (pintype "input"))
      (node (ref "USB1") (pin "2") (pinfunction "VBUS_2") (pintype "input"))
    )
    (net (code "35") (name "Net-(Q1-B)") (class "Default")
      (node (ref "Q1") (pin "1") (pinfunction "B_1") (pintype "input"))
      (node (ref "Q2") (pin "3") (pinfunction "C_3") (pintype "input"))
      (node (ref "R46") (pin "2") (pinfunction "2_2") (pintype "input"))
      (node (ref "U13") (pin "5") (pinfunction "IN2+_5") (pintype "input"))
    )
    (net (code "36") (name "Net-(Q3-B)") (class "Default")
      (node (ref "Q3") (pin "1") (pinfunction "B_1") (pintype "input"))
      (node (ref "Q4") (pin "3") (pinfunction "C_3") (pintype "input"))
      (node (ref "R47") (pin "2") (pinfunction "2_2") (pintype "input"))
      (node (ref "U13") (pin "3") (pinfunction "IN1+_3") (pintype "input"))
    )
    (net (code "37") (name "Net-(R10-Pad2)") (class "Default")
      (node (ref "R10") (pin "2") (pinfunction "2_2") (pintype "input"))
      (node (ref "R11") (pin "2") (pinfunction "2_2") (pintype "input"))
      (node (ref "R9") (pin "1") (pinfunction "1_1") (pintype "input"))
    )
    (net (code "38") (name "Net-(R19-Pad1)") (class "Default")
      (node (ref "R19") (pin "1") (pinfunction "1_1") (pintype "input"))
      (node (ref "R20") (pin "2") (pinfunction "2_2") (pintype "input"))
    )
    (net (code "39") (name "Net-(R20-Pad1)") (class "Default")
      (node (ref "R20") (pin "1") (pinfunction "1_1") (pintype "input"))
      (node (ref "R21") (pin "2") (pinfunction "2_2") (pintype "input"))
    )
    (net (code "40") (name "Net-(R22-Pad1)") (class "Default")
      (node (ref "R22") (pin "1") (pinfunction "1_1") (pintype "input"))
      (node (ref "R23") (pin "2") (pinfunction "2_2") (pintype "input"))
    )
    (net (code "41") (name "Net-(R23-Pad1)") (class "Default")
      (node (ref "R23") (pin "1") (pinfunction "1_1") (pintype "input"))
      (node (ref "R54") (pin "2") (pinfunction "2_2") (pintype "input"))
    )
    (net (code "42") (name "Net-(U1-PA2)") (class "Default")
      (node (ref "SW5") (pin "2") (pinfunction "2_2") (pintype "input"))
      (node (ref "U1") (pin "13") (pinfunction "PA2_13") (pintype "input"))
    )
    (net (code "43") (name "Net-(U1-PA3)") (class "Default")
      (node (ref "SW4") (pin "2") (pinfunction "2_2") (pintype "input"))
      (node (ref "U1") (pin "14") (pinfunction "PA3_14") (pintype "input"))
    )
    (net (code "44") (name "Net-(U1-PA13-SWD)") (class "Default")
      (node (ref "H8") (pin "1") (pinfunction "1_1") (pintype "unspecified"))
      (node (ref "U1") (pin "2") (pinfunction "PA13-SWD_2") (pintype "input"))
    )
    (net (code "45") (name "Net-(U1-PA14-SWC)") (class "Default")
      (node (ref "H9") (pin "1") (pinfunction "1_1") (pintype "unspecified"))
      (node (ref "U1") (pin "3") (pinfunction "PA14-SWC_3") (pintype "input"))
    )
    (net (code "46") (name "Net-(U1-PB6{slash}PF4-BOOT0)") (class "Default")
      (node (ref "R7") (pin "2") (pinfunction "2_2") (pintype "input"))
      (node (ref "U1") (pin "5") (pinfunction "PB6/PF4-BOOT0_5") (pintype "input"))
    )
    (net (code "47") (name "Net-(U1-PF0-OSCIN)") (class "Default")
      (node (ref "C1") (pin "1") (pinfunction "1_1") (pintype "input"))
      (node (ref "U1") (pin "8") (pinfunction "PF0-OSCIN_8") (pintype "input"))
      (node (ref "X1") (pin "1") (pinfunction "1_1") (pintype "input"))
    )
    (net (code "48") (name "Net-(U1-PF1-OSCOUT)") (class "Default")
      (node (ref "C2") (pin "2") (pinfunction "2_2") (pintype "input"))
      (node (ref "U1") (pin "9") (pinfunction "PF1-OSCOUT_9") (pintype "input"))
      (node (ref "X1") (pin "3") (pinfunction "3_3") (pintype "input"))
    )
    (net (code "49") (name "Net-(U1-PF2-NRST)") (class "Default")
      (node (ref "C3") (pin "2") (pinfunction "2_2") (pintype "input"))
      (node (ref "U1") (pin "10") (pinfunction "PF2-NRST_10") (pintype "input"))
    )
    (net (code "50") (name "Net-(U2A-IN1+)") (class "Default")
      (node (ref "C15") (pin "1") (pinfunction "1_1") (pintype "input"))
      (node (ref "R18") (pin "1") (pinfunction "1_1") (pintype "input"))
      (node (ref "R30") (pin "2") (pinfunction "2_2") (pintype "input"))
      (node (ref "U2") (pin "3") (pinfunction "IN1+_3") (pintype "input"))
    )
    (net (code "51") (name "Net-(U2A-IN1-)") (class "Default")
      (node (ref "R17") (pin "2") (pinfunction "2_2") (pintype "input"))
      (node (ref "U2") (pin "1") (pinfunction "OUT_1") (pintype "output"))
      (node (ref "U2") (pin "2") (pinfunction "IN1-_2") (pintype "input"))
    )
    (net (code "52") (name "Net-(U2B-IN2+)") (class "Default")
      (node (ref "R17") (pin "1") (pinfunction "1_1") (pintype "input"))
      (node (ref "R27") (pin "2") (pinfunction "2_2") (pintype "input"))
      (node (ref "U2") (pin "5") (pinfunction "IN2+_5") (pintype "input"))
    )
    (net (code "53") (name "Net-(U2B-IN2-)") (class "Default")
      (node (ref "R28") (pin "2") (pinfunction "2_2") (pintype "input"))
      (node (ref "R29") (pin "2") (pinfunction "2_2") (pintype "input"))
      (node (ref "U2") (pin "6") (pinfunction "IN2-_6") (pintype "input"))
    )
    (net (code "54") (name "Net-(U5-A)") (class "Default")
      (node (ref "C37") (pin "2") (pinfunction "2_2") (pintype "input"))
      (node (ref "U5") (pin "4") (pinfunction "A_4") (pintype "input"))
    )
    (net (code "55") (name "Net-(U5-B0)") (class "Default")
      (node (ref "R19") (pin "2") (pinfunction "2_2") (pintype "input"))
      (node (ref "R53") (pin "1") (pinfunction "1_1") (pintype "input"))
      (node (ref "U5") (pin "3") (pinfunction "B0_3") (pintype "input"))
    )
    (net (code "56") (name "Net-(U6-CHRG#)") (class "Default")
      (node (ref "R12") (pin "1") (pinfunction "1_1") (pintype "input"))
      (node (ref "U6") (pin "7") (pinfunction "CHRG#_7") (pintype "input"))
    )
    (net (code "57") (name "Net-(U6-PROG)") (class "Default")
      (node (ref "R9") (pin "2") (pinfunction "2_2") (pintype "input"))
      (node (ref "U6") (pin "2") (pinfunction "PROG_2") (pintype "input"))
    )
    (net (code "58") (name "Net-(U6-STDBY#)") (class "Default")
      (node (ref "R13") (pin "1") (pinfunction "1_1") (pintype "input"))
      (node (ref "U6") (pin "6") (pinfunction "STDBY#_6") (pintype "input"))
    )
    (net (code "59") (name "Net-(U7-CS)") (class "Default")
      (node (ref "R8") (pin "2") (pinfunction "2_2") (pintype "input"))
      (node (ref "U7") (pin "2") (pinfunction "CS_2") (pintype "input"))
    )
    (net (code "60") (name "Net-(U7-OC)") (class "Default")
      (node (ref "U7") (pin "3") (pinfunction "OC_3") (pintype "input"))
      (node (ref "U9") (pin "1") (pinfunction "G_1") (pintype "input"))
    )
    (net (code "61") (name "Net-(U7-OD)") (class "Default")
      (node (ref "U7") (pin "1") (pinfunction "OD_1") (pintype "input"))
      (node (ref "U8") (pin "1") (pinfunction "G_1") (pintype "input"))
    )
    (net (code "62") (name "Net-(U7-VCC)") (class "Default")
      (node (ref "C8") (pin "1") (pinfunction "1_1") (pintype "input"))
      (node (ref "R16") (pin "1") (pinfunction "1_1") (pintype "input"))
      (node (ref "U7") (pin "5") (pinfunction "VCC_5") (pintype "input"))
    )
    (net (code "63") (name "Net-(U8-D)") (class "Default")
      (node (ref "U8") (pin "3") (pinfunction "D_3") (pintype "input"))
      (node (ref "U9") (pin "3") (pinfunction "D_3") (pintype "input"))
    )
    (net (code "64") (name "Net-(U13A-IN1-)") (class "Default")
      (node (ref "C25") (pin "1") (pinfunction "1_1") (pintype "input"))
      (node (ref "R37") (pin "1") (pinfunction "1_1") (pintype "input"))
      (node (ref "R39") (pin "2") (pinfunction "2_2") (pintype "input"))
      (node (ref "U13") (pin "2") (pinfunction "IN1-_2") (pintype "input"))
    )
    (net (code "65") (name "Net-(U13A-OUT)") (class "Default")
      (node (ref "C25") (pin "2") (pinfunction "2_2") (pintype "input"))
      (node (ref "R37") (pin "2") (pinfunction "2_2") (pintype "input"))
      (node (ref "R45") (pin "1") (pinfunction "1_1") (pintype "input"))
      (node (ref "U13") (pin "1") (pinfunction "OUT_1") (pintype "output"))
    )
    (net (code "66") (name "Net-(U13B-IN2-)") (class "Default")
      (node (ref "C26") (pin "1") (pinfunction "1_1") (pintype "input"))
      (node (ref "R38") (pin "1") (pinfunction "1_1") (pintype "input"))
      (node (ref "R39") (pin "1") (pinfunction "1_1") (pintype "input"))
      (node (ref "U13") (pin "6") (pinfunction "IN2-_6") (pintype "input"))
    )
    (net (code "67") (name "Net-(U13B-OUT2)") (class "Default")
      (node (ref "C26") (pin "2") (pinfunction "2_2") (pintype "input"))
      (node (ref "R38") (pin "2") (pinfunction "2_2") (pintype "input"))
      (node (ref "R43") (pin "1") (pinfunction "1_1") (pintype "input"))
      (node (ref "U13") (pin "7") (pinfunction "OUT2_7") (pintype "output"))
    )
    (net (code "68") (name "Net-(U14A-IN1+)") (class "Default")
      (node (ref "R44") (pin "1") (pinfunction "1_1") (pintype "input"))
      (node (ref "R45") (pin "2") (pinfunction "2_2") (pintype "input"))
      (node (ref "U14") (pin "3") (pinfunction "IN1+_3") (pintype "input"))
    )
    (net (code "69") (name "Net-(U14A-IN1-)") (class "Default")
      (node (ref "R42") (pin "1") (pinfunction "1_1") (pintype "input"))
      (node (ref "R43") (pin "2") (pinfunction "2_2") (pintype "input"))
      (node (ref "U14") (pin "2") (pinfunction "IN1-_2") (pintype "input"))
    )
    (net (code "70") (name "Net-(U14A-OUT)") (class "Default")
      (node (ref "R42") (pin "2") (pinfunction "2_2") (pintype "input"))
      (node (ref "R53") (pin "2") (pinfunction "2_2") (pintype "input"))
      (node (ref "U14") (pin "1") (pinfunction "OUT_1") (pintype "output"))
      (node (ref "U5") (pin "1") (pinfunction "B1_1") (pintype "input"))
    )
    (net (code "71") (name "Net-(U14B-IN2+)") (class "Default")
      (node (ref "C37") (pin "1") (pinfunction "1_1") (pintype "input"))
      (node (ref "R56") (pin "2") (pinfunction "2_2") (pintype "input"))
      (node (ref "R57") (pin "1") (pinfunction "1_1") (pintype "input"))
      (node (ref "U14") (pin "5") (pinfunction "IN2+_5") (pintype "input"))
    )
    (net (code "72") (name "Net-(U14B-IN2-)") (class "Default")
      (node (ref "C36") (pin "1") (pinfunction "1_1") (pintype "input"))
      (node (ref "R22") (pin "2") (pinfunction "2_2") (pintype "input"))
      (node (ref "R55") (pin "1") (pinfunction "1_1") (pintype "input"))
      (node (ref "U14") (pin "6") (pinfunction "IN2-_6") (pintype "input"))
    )
    (net (code "73") (name "Net-(USB1-CC1)") (class "Default")
      (node (ref "R14") (pin "2") (pinfunction "2_2") (pintype "input"))
      (node (ref "USB1") (pin "4") (pinfunction "CC1_4") (pintype "input"))
    )
    (net (code "74") (name "Net-(USB1-CC2)") (class "Default")
      (node (ref "R15") (pin "2") (pinfunction "2_2") (pintype "input"))
      (node (ref "USB1") (pin "10") (pinfunction "CC2_10") (pintype "input"))
    )
    (net (code "75") (name "VCC") (class "Default")
      (node (ref "C12") (pin "2") (pinfunction "2_2") (pintype "input"))
      (node (ref "C9") (pin "2") (pinfunction "2_2") (pintype "input"))
      (node (ref "R18") (pin "2") (pinfunction "2_2") (pintype "input"))
      (node (ref "SW1") (pin "1") (pinfunction "1_1") (pintype "input"))
      (node (ref "U2") (pin "8") (pinfunction "VCC_8") (pintype "input"))
      (node (ref "U4") (pin "3") (pinfunction "VIN_3") (pintype "input"))
    )
    (net (code "76") (name "unconnected-(Q1-E-Pad2)") (class "Default")
      (node (ref "Q1") (pin "2") (pinfunction "E_2") (pintype "input+no_connect"))
    )
    (net (code "77") (name "unconnected-(Q2-E-Pad2)") (class "Default")
      (node (ref "Q2") (pin "2") (pinfunction "E_2") (pintype "input+no_connect"))
    )
    (net (code "78") (name "unconnected-(Q3-E-Pad2)") (class "Default")
      (node (ref "Q3") (pin "2") (pinfunction "E_2") (pintype "input+no_connect"))
    )
    (net (code "79") (name "unconnected-(Q4-E-Pad2)") (class "Default")
      (node (ref "Q4") (pin "2") (pinfunction "E_2") (pintype "input+no_connect"))
    )
    (net (code "80") (name "unconnected-(U1-PA6-Pad6)") (class "Default")
      (node (ref "U1") (pin "6") (pinfunction "PA6_6") (pintype "input"))
    )
    (net (code "81") (name "unconnected-(U1-PB1-Pad19)") (class "Default")
      (node (ref "U1") (pin "19") (pinfunction "PB1_19") (pintype "input"))
    )
    (net (code "82") (name "unconnected-(U1-PB2-Pad18)") (class "Default")
      (node (ref "U1") (pin "18") (pinfunction "PB2_18") (pintype "input"))
    )
    (net (code "83") (name "unconnected-(U7-TD-Pad4)") (class "Default")
      (node (ref "U7") (pin "4") (pinfunction "TD_4") (pintype "input"))
    )
    (net (code "84") (name "unconnected-(USB1-DN1-Pad7)") (class "Default")
      (node (ref "USB1") (pin "7") (pinfunction "DN1_7") (pintype "input"))
    )
    (net (code "85") (name "unconnected-(USB1-DN2-Pad5)") (class "Default")
      (node (ref "USB1") (pin "5") (pinfunction "DN2_5") (pintype "input"))
    )
    (net (code "86") (name "unconnected-(USB1-DP1-Pad6)") (class "Default")
      (node (ref "USB1") (pin "6") (pinfunction "DP1_6") (pintype "input"))
    )
    (net (code "87") (name "unconnected-(USB1-DP2-Pad8)") (class "Default")
      (node (ref "USB1") (pin "8") (pinfunction "DP2_8") (pintype "input"))
    )
    (net (code "88") (name "unconnected-(USB1-SBU1-Pad9)") (class "Default")
      (node (ref "USB1") (pin "9") (pinfunction "SBU1_9") (pintype "input"))
    )
    (net (code "89") (name "unconnected-(USB1-SBU2-Pad3)") (class "Default")
      (node (ref "USB1") (pin "3") (pinfunction "SBU2_3") (pintype "input"))
    )
  )
)
